# Tiny45Logic.net
KiCad netlist of a schematic drawn in EAGLE
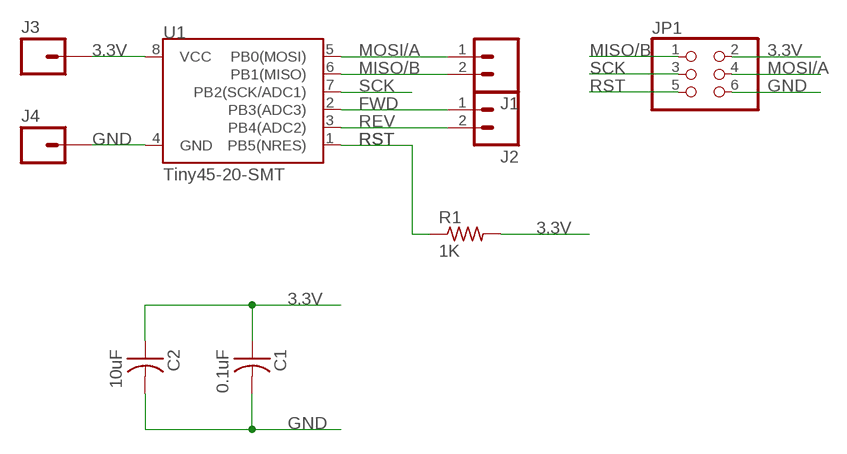
[diagram p0: schematic, sheet 1]

(export (version "E")
  (design (tool "Eeschema 10.0.6"))
  (components
    (comp (ref "C1")
      (value "0.1uF")
      (footprint "eagle-import:C1206FAB")
      (libsource (lib "eagle-import") (part "CAP-US1206FAB"))
    )
    (comp (ref "C2")
      (value "10uF")
      (footprint "eagle-import:C1206FAB")
      (libsource (lib "eagle-import") (part "CAP-US1206FAB"))
    )
    (comp (ref "J1")
      (value "M02PTH")
      (footprint "eagle-import:1X02")
      (libsource (lib "eagle-import") (part "M02PTH"))
    )
    (comp (ref "J2")
      (value "M02PTH")
      (footprint "eagle-import:1X02")
      (libsource (lib "eagle-import") (part "M02PTH"))
    )
    (comp (ref "J3")
      (value "M01PTH")
      (footprint "eagle-import:1X01")
      (libsource (lib "eagle-import") (part "M01PTH"))
    )
    (comp (ref "J4")
      (value "M01PTH")
      (footprint "eagle-import:1X01")
      (libsource (lib "eagle-import") (part "M01PTH"))
    )
    (comp (ref "JP1")
      (value "PINHD-2X3-SMD")
      (footprint "eagle-import:2X03SMD")
      (libsource (lib "eagle-import") (part "PINHD-2X3-SMD"))
    )
    (comp (ref "R1")
      (value "1K")
      (footprint "eagle-import:R1206")
      (libsource (lib "eagle-import") (part "RES-US1206"))
    )
    (comp (ref "U1")
      (value "Tiny45-20-SMT")
      (footprint "eagle-import:SO08-EIAJ")
      (libsource (lib "eagle-import") (part "ATTINY45TINY45-20-SMT"))
    )
  )
  (nets
    (net (code "1") (name "/3.3V") (class "Default")
      (node (ref "C1") (pin "1") (pinfunction "1_1") (pintype "passive"))
      (node (ref "C2") (pin "1") (pinfunction "1_1") (pintype "passive"))
      (node (ref "J3") (pin "1") (pinfunction "1_1") (pintype "passive"))
      (node (ref "JP1") (pin "2") (pinfunction "2_2") (pintype "passive"))
      (node (ref "R1") (pin "2") (pinfunction "2_2") (pintype "passive"))
      (node (ref "U1") (pin "8") (pinfunction "VCC_8") (pintype "bidirectional"))
    )
    (net (code "2") (name "/FWD") (class "Default")
      (node (ref "J2") (pin "1") (pinfunction "1_1") (pintype "passive"))
      (node (ref "U1") (pin "2") (pinfunction "PB3(ADC3)_2") (pintype "bidirectional"))
    )
    (net (code "3") (name "/GND") (class "Default")
      (node (ref "C1") (pin "2") (pinfunction "2_2") (pintype "passive"))
      (node (ref "C2") (pin "2") (pinfunction "2_2") (pintype "passive"))
      (node (ref "J4") (pin "1") (pinfunction "1_1") (pintype "passive"))
      (node (ref "JP1") (pin "6") (pinfunction "6_6") (pintype "passive"))
      (node (ref "U1") (pin "4") (pinfunction "GND_4") (pintype "bidirectional"))
    )
    (net (code "4") (name "/MISO{slash}B") (class "Default")
      (node (ref "J1") (pin "2") (pinfunction "2_2") (pintype "passive"))
      (node (ref "JP1") (pin "1") (pinfunction "1_1") (pintype "passive"))
      (node (ref "U1") (pin "6") (pinfunction "PB1(MISO)_6") (pintype "bidirectional"))
    )
    (net (code "5") (name "/MOSI{slash}A") (class "Default")
      (node (ref "J1") (pin "1") (pinfunction "1_1") (pintype "passive"))
      (node (ref "JP1") (pin "4") (pinfunction "4_4") (pintype "passive"))
      (node (ref "U1") (pin "5") (pinfunction "PB0(MOSI)_5") (pintype "bidirectional"))
    )
    (net (code "6") (name "/REV") (class "Default")
      (node (ref "J2") (pin "2") (pinfunction "2_2") (pintype "passive"))
      (node (ref "U1") (pin "3") (pinfunction "PB4(ADC2)_3") (pintype "bidirectional"))
    )
    (net (code "7") (name "/RST") (class "Default")
      (node (ref "JP1") (pin "5") (pinfunction "5_5") (pintype "passive"))
      (node (ref "R1") (pin "1") (pinfunction "1_1") (pintype "passive"))
      (node (ref "U1") (pin "1") (pinfunction "PB5(NRES)_1") (pintype "bidirectional"))
    )
    (net (code "8") (name "/SCK") (class "Default")
      (node (ref "JP1") (pin "3") (pinfunction "3_3") (pintype "passive"))
      (node (ref "U1") (pin "7") (pinfunction "PB2(SCK/ADC1)_7") (pintype "bidirectional"))
    )
  )
)
